# Power_Switch.net
KiCad netlist of a schematic drawn in Altium Designer
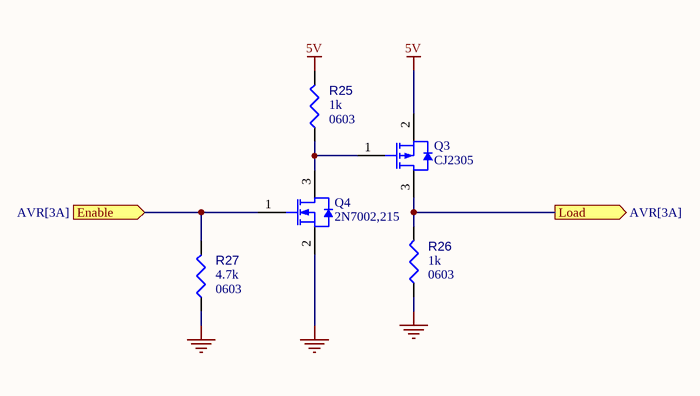
[diagram p0: Power Switch.SchDoc]

(export (version "E")
  (design (tool "Eeschema 10.0.6"))
  (components
    (comp (ref "Q3")
      (value "CJ2305")
      (footprint "JSCJ-SOT23-3_V")
      (description "P-Channel Plastic Encapsulate MOSFET, 12 V, 4.1 A, 3-Pin SOT23, Tape and Reel")
      (fields (field (name "MANUFACTURER") "Jiangsu Changjiang Electronics Technology"))
      (libsource (lib "Twill Technology Inc") (part "PEMOS-GSD-3"))
    )
    (comp (ref "Q4")
      (value "2N7002,215")
      (footprint "NXP-SOT23-3_V")
      (fields (field (name "POWER") "830mW") (field (name "MANUFACTURER") "NXP Semiconductors"))
      (libsource (lib "Twill Technology Inc") (part "NEMOS-GSD-3"))
    )
    (comp (ref "R25")
      (value "1k")
      (footprint "RESC1608X55X25ML10T15")
      (description "Chip Resistor, 1 KOhm, +/-1%, 0.1 W, -55 to 155 degC, 0603 (1608 Metric)")
      (fields
        (field (name "CASE/PACKAGE") "0603")
        (field (name "POWER") "100mW")
        (field (name "TOLERANCE") "1%")
      )
      (libsource (lib "Twill Technology Inc") (part "RES-2"))
    )
    (comp (ref "R26")
      (value "1k")
      (footprint "RESC1608X55X25ML10T15")
      (description "Chip Resistor, 1 KOhm, +/-1%, 0.1 W, -55 to 155 degC, 0603 (1608 Metric)")
      (fields
        (field (name "CASE/PACKAGE") "0603")
        (field (name "POWER") "100mW")
        (field (name "TOLERANCE") "1%")
      )
      (libsource (lib "Twill Technology Inc") (part "RES-2"))
    )
    (comp (ref "R27")
      (value "4.7k")
      (footprint "RESC1608X55X25ML10T15")
      (description "Chip Resistor, 1 KOhm, +/-1%, 0.1 W, -55 to 155 degC, 0603 (1608 Metric)")
      (fields
        (field (name "CASE/PACKAGE") "0603")
        (field (name "POWER") "100mW")
        (field (name "TOLERANCE") "1%")
      )
      (libsource (lib "Twill Technology Inc") (part "RES-2"))
    )
  )
  (nets
    (net (code "1") (name "/Enable") (class "Default")
      (node (ref "Q4") (pin "1") (pinfunction "G_1") (pintype "passive"))
      (node (ref "R27") (pin "2") (pinfunction "2_2") (pintype "passive"))
    )
    (net (code "2") (name "/Load") (class "Default")
      (node (ref "Q3") (pin "3") (pinfunction "DRAIN_3") (pintype "passive"))
      (node (ref "R26") (pin "2") (pinfunction "2_2") (pintype "passive"))
    )
    (net (code "3") (name "5V") (class "Default")
      (node (ref "Q3") (pin "2") (pinfunction "SOURCE_2") (pintype "passive"))
      (node (ref "R25") (pin "2") (pinfunction "2_2") (pintype "passive"))
    )
    (net (code "4") (name "GND") (class "Default")
      (node (ref "Q4") (pin "2") (pinfunction "S_2") (pintype "passive"))
      (node (ref "R26") (pin "1") (pinfunction "1_1") (pintype "passive"))
      (node (ref "R27") (pin "1") (pinfunction "1_1") (pintype "passive"))
    )
    (net (code "5") (name "Net-(Q3-GATE)") (class "Default")
      (node (ref "Q3") (pin "1") (pinfunction "GATE_1") (pintype "passive"))
      (node (ref "Q4") (pin "3") (pinfunction "D_3") (pintype "passive"))
      (node (ref "R25") (pin "1") (pinfunction "1_1") (pintype "passive"))
    )
  )
)
